# lcd.net
KiCad netlist of a schematic drawn in Altium Designer
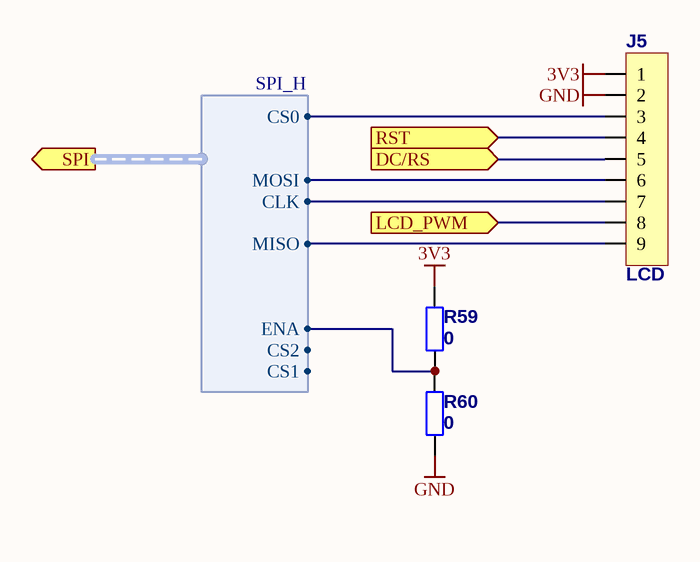
[diagram p0: lcd.SchDoc]

(export (version "E")
  (design (tool "Eeschema 10.0.6"))
  (components
    (comp (ref "J5") (value "LCD") (footprint "GP_9x1H") (libsource (lib "goldpin_male") (part "CN_9x1")))
    (comp (ref "R59")
      (value "0")
      (footprint "R0402")
      (description "Resistor")
      (libsource (lib "resistors") (part "Res"))
    )
    (comp (ref "R60")
      (value "0")
      (footprint "R0402")
      (description "Resistor")
      (libsource (lib "resistors") (part "Res"))
    )
  )
  (nets
    (net (code "2") (name "/CLK") (class "Default")
      (node (ref "J5") (pin "7") (pinfunction "7_7") (pintype "passive"))
    )
    (net (code "3") (name "/CS0") (class "Default")
      (node (ref "J5") (pin "3") (pinfunction "3_3") (pintype "passive"))
    )
    (net (code "4") (name "/DC{slash}RS") (class "Default")
      (node (ref "J5") (pin "5") (pinfunction "5_5") (pintype "passive"))
    )
    (net (code "5") (name "/ENA") (class "Default")
      (node (ref "R59") (pin "2") (pinfunction "2_2") (pintype "passive"))
      (node (ref "R60") (pin "1") (pinfunction "1_1") (pintype "passive"))
    )
    (net (code "6") (name "/LCD_PWM") (class "Default")
      (node (ref "J5") (pin "8") (pinfunction "8_8") (pintype "passive"))
    )
    (net (code "7") (name "/MISO") (class "Default")
      (node (ref "J5") (pin "9") (pinfunction "9_9") (pintype "passive"))
    )
    (net (code "8") (name "/MOSI") (class "Default")
      (node (ref "J5") (pin "6") (pinfunction "6_6") (pintype "passive"))
    )
    (net (code "9") (name "/RST") (class "Default")
      (node (ref "J5") (pin "4") (pinfunction "4_4") (pintype "passive"))
    )
    (net (code "11") (name "3V3") (class "Default")
      (node (ref "J5") (pin "1") (pinfunction "1_1") (pintype "passive"))
      (node (ref "R59") (pin "1") (pinfunction "1_1") (pintype "passive"))
    )
    (net (code "12") (name "GND") (class "Default")
      (node (ref "J5") (pin "2") (pinfunction "2_2") (pintype "passive"))
      (node (ref "R60") (pin "2") (pinfunction "2_2") (pintype "passive"))
    )
  )
)
